# xc9141-xc9142.net
KiCad netlist of a schematic drawn in EAGLE
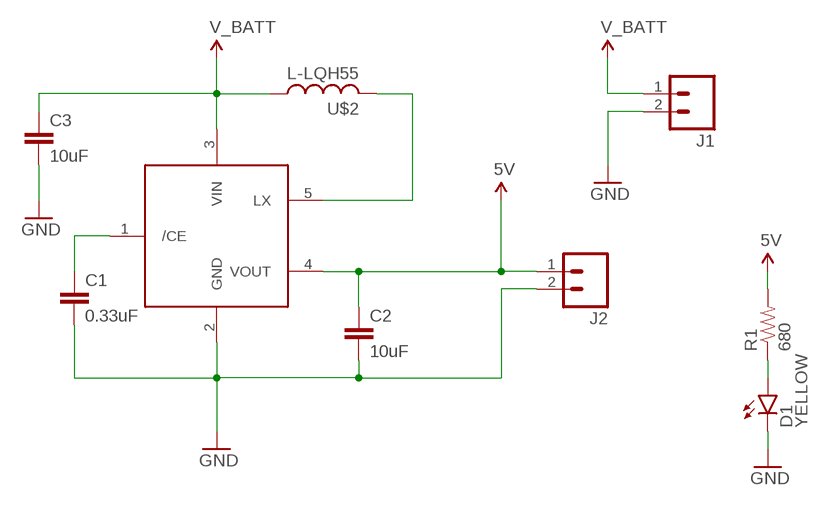
[diagram p0: schematic, sheet 1]

(export (version "E")
  (design (tool "Eeschema 10.0.6"))
  (components
    (comp (ref "C1")
      (value "0.33uF")
      (footprint "eagle-import:0805-CAP")
      (libsource (lib "eagle-import") (part "0.33UF-50V-10%(0805)"))
    )
    (comp (ref "C2")
      (value "10uF")
      (footprint "eagle-import:1206")
      (libsource (lib "eagle-import") (part "10UF-6.3V-20%(1206)"))
    )
    (comp (ref "C3")
      (value "10uF")
      (footprint "eagle-import:1206")
      (libsource (lib "eagle-import") (part "10UF-6.3V-20%(1206)"))
    )
    (comp (ref "D1")
      (value "YELLOW")
      (footprint "eagle-import:LED-1206")
      (libsource (lib "eagle-import") (part "LED-YELLOW1206"))
    )
    (comp (ref "J1")
      (value "M02JST-PTH-VERT")
      (footprint "eagle-import:JST-2-PTH-VERT")
      (libsource (lib "eagle-import") (part "M02JST-PTH-VERT"))
    )
    (comp (ref "J2")
      (value "M02PTH3")
      (footprint "eagle-import:1X02_LONGPADS")
      (libsource (lib "eagle-import") (part "M02PTH3"))
    )
    (comp (ref "R1")
      (value "680")
      (footprint "eagle-import:0805")
      (libsource (lib "eagle-import") (part "0.3OHM-1/8W-1%(0805)"))
    )
    (comp (ref "U$1")
      (value "XC9141/XC9142SOT-25")
      (footprint "eagle-import:SOT-25")
      (libsource (lib "eagle-import") (part "XC9141/XC9142SOT-25"))
    )
    (comp (ref "U$2")
      (value "L-LQH55")
      (footprint "eagle-import:LQH55")
      (libsource (lib "eagle-import") (part "L-LQH55"))
    )
  )
  (nets
    (net (code "1") (name "5V") (class "Default")
      (node (ref "C2") (pin "1") (pinfunction "1_1") (pintype "passive"))
      (node (ref "J2") (pin "1") (pinfunction "1_1") (pintype "passive"))
      (node (ref "R1") (pin "2") (pinfunction "2_2") (pintype "passive"))
      (node (ref "U$1") (pin "4") (pinfunction "VOUT_4") (pintype "bidirectional"))
    )
    (net (code "2") (name "GND") (class "Default")
      (node (ref "C1") (pin "2") (pinfunction "2_2") (pintype "passive"))
      (node (ref "C2") (pin "2") (pinfunction "2_2") (pintype "passive"))
      (node (ref "C3") (pin "2") (pinfunction "2_2") (pintype "passive"))
      (node (ref "D1") (pin "C") (pinfunction "C_C") (pintype "passive"))
      (node (ref "J1") (pin "2") (pinfunction "2_2") (pintype "passive"))
      (node (ref "J2") (pin "2") (pinfunction "2_2") (pintype "passive"))
      (node (ref "U$1") (pin "2") (pinfunction "GND_2") (pintype "bidirectional"))
    )
    (net (code "3") (name "Net-(D1-PadA)") (class "Default")
      (node (ref "D1") (pin "A") (pinfunction "A_A") (pintype "passive"))
      (node (ref "R1") (pin "1") (pinfunction "1_1") (pintype "passive"))
    )
    (net (code "4") (name "Net-(U$1-LX)") (class "Default")
      (node (ref "U$1") (pin "5") (pinfunction "LX_5") (pintype "bidirectional"))
      (node (ref "U$2") (pin "2") (pinfunction "2_2") (pintype "passive"))
    )
    (net (code "5") (name "Net-(U$1-{slash}CE)") (class "Default")
      (node (ref "C1") (pin "1") (pinfunction "1_1") (pintype "passive"))
      (node (ref "U$1") (pin "1") (pinfunction "/CE_1") (pintype "bidirectional"))
    )
    (net (code "6") (name "V_BATT") (class "Default")
      (node (ref "C3") (pin "1") (pinfunction "1_1") (pintype "passive"))
      (node (ref "J1") (pin "1") (pinfunction "1_1") (pintype "passive"))
      (node (ref "U$1") (pin "3") (pinfunction "VIN_3") (pintype "bidirectional"))
      (node (ref "U$2") (pin "1") (pinfunction "1_1") (pintype "passive"))
    )
  )
)
